# table4_vd2.net
KiCad netlist of a schematic drawn in EasyEDA
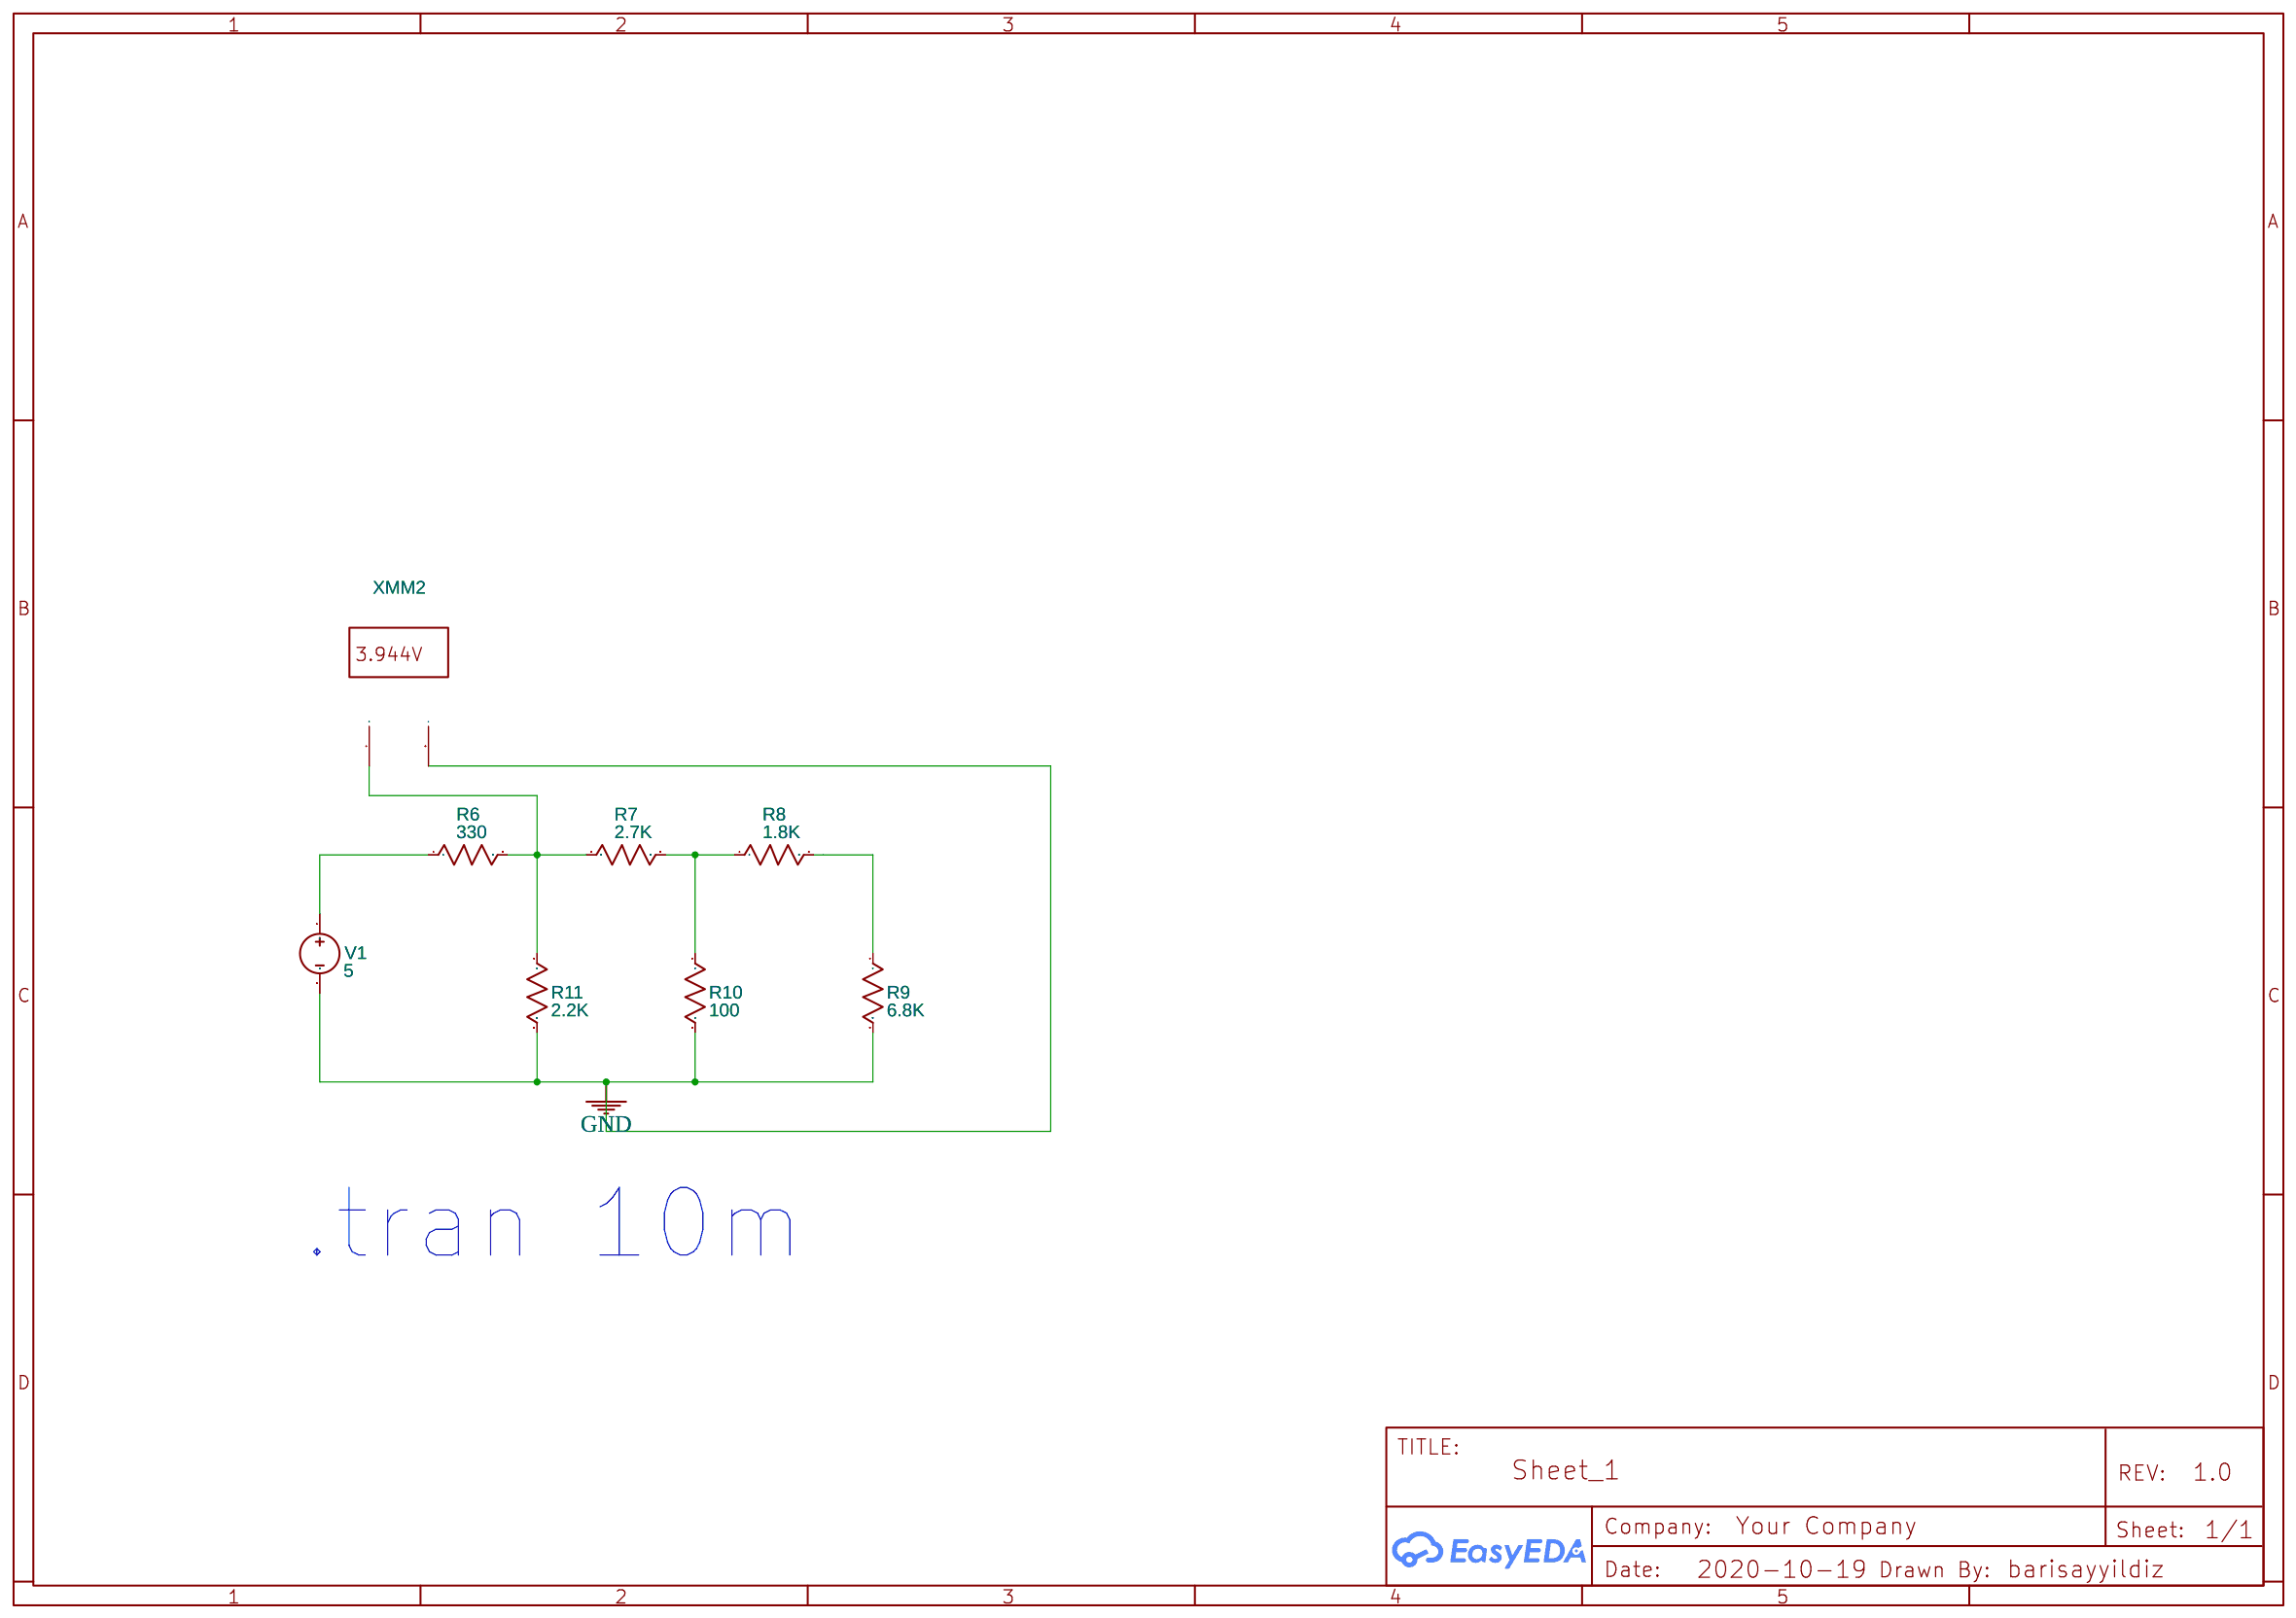
[diagram p0: schematic sheet]

(export (version "E")
  (design (tool "Eeschema 10.0.6"))
  (components
    (comp (ref "R6") (value "330") (libsource (lib "") (part "Resistor_US_1")))
    (comp (ref "R7") (value "2.7K") (libsource (lib "") (part "Resistor_US_1")))
    (comp (ref "R8") (value "1.8K") (libsource (lib "") (part "Resistor_US_1")))
    (comp (ref "R9") (value "6.8K") (libsource (lib "") (part "Resistor_US")))
    (comp (ref "R10") (value "100") (libsource (lib "") (part "Resistor_US")))
    (comp (ref "R11") (value "2.2K") (libsource (lib "") (part "Resistor_US")))
    (comp (ref "V1") (value "5") (libsource (lib "") (part "VDC")))
    (comp (ref "XMM2") (value "Multimeter") (libsource (lib "") (part "MULTIMETER")))
  )
  (nets
    (net (code "1") (name "GND") (class "Default")
      (node (ref "R10") (pin "2") (pinfunction "2_2") (pintype "unspecified"))
      (node (ref "R11") (pin "2") (pinfunction "2_2") (pintype "unspecified"))
      (node (ref "R9") (pin "2") (pinfunction "2_2") (pintype "unspecified"))
      (node (ref "V1") (pin "2") (pinfunction "2_2") (pintype "unspecified"))
      (node (ref "XMM2") (pin "2") (pinfunction "I_2") (pintype "unspecified"))
    )
    (net (code "2") (name "Net-(R6-Pad1)") (class "Default")
      (node (ref "R6") (pin "1") (pinfunction "1_1") (pintype "unspecified"))
      (node (ref "V1") (pin "1") (pinfunction "1_1") (pintype "unspecified"))
    )
    (net (code "3") (name "Net-(R8-Pad2)") (class "Default")
      (node (ref "R8") (pin "2") (pinfunction "2_2") (pintype "unspecified"))
      (node (ref "R9") (pin "1") (pinfunction "1_1") (pintype "unspecified"))
    )
    (net (code "4") (name "Net-(R10-Pad1)") (class "Default")
      (node (ref "R10") (pin "1") (pinfunction "1_1") (pintype "unspecified"))
      (node (ref "R7") (pin "2") (pinfunction "2_2") (pintype "unspecified"))
      (node (ref "R8") (pin "1") (pinfunction "1_1") (pintype "unspecified"))
    )
    (net (code "5") (name "Net-(XMM2-+)") (class "Default")
      (node (ref "R11") (pin "1") (pinfunction "1_1") (pintype "unspecified"))
      (node (ref "R6") (pin "2") (pinfunction "2_2") (pintype "unspecified"))
      (node (ref "R7") (pin "1") (pinfunction "1_1") (pintype "unspecified"))
      (node (ref "XMM2") (pin "1") (pinfunction "+_1") (pintype "unspecified"))
    )
  )
)
